# CKT-2000.net
KiCad netlist of a schematic drawn in EAGLE
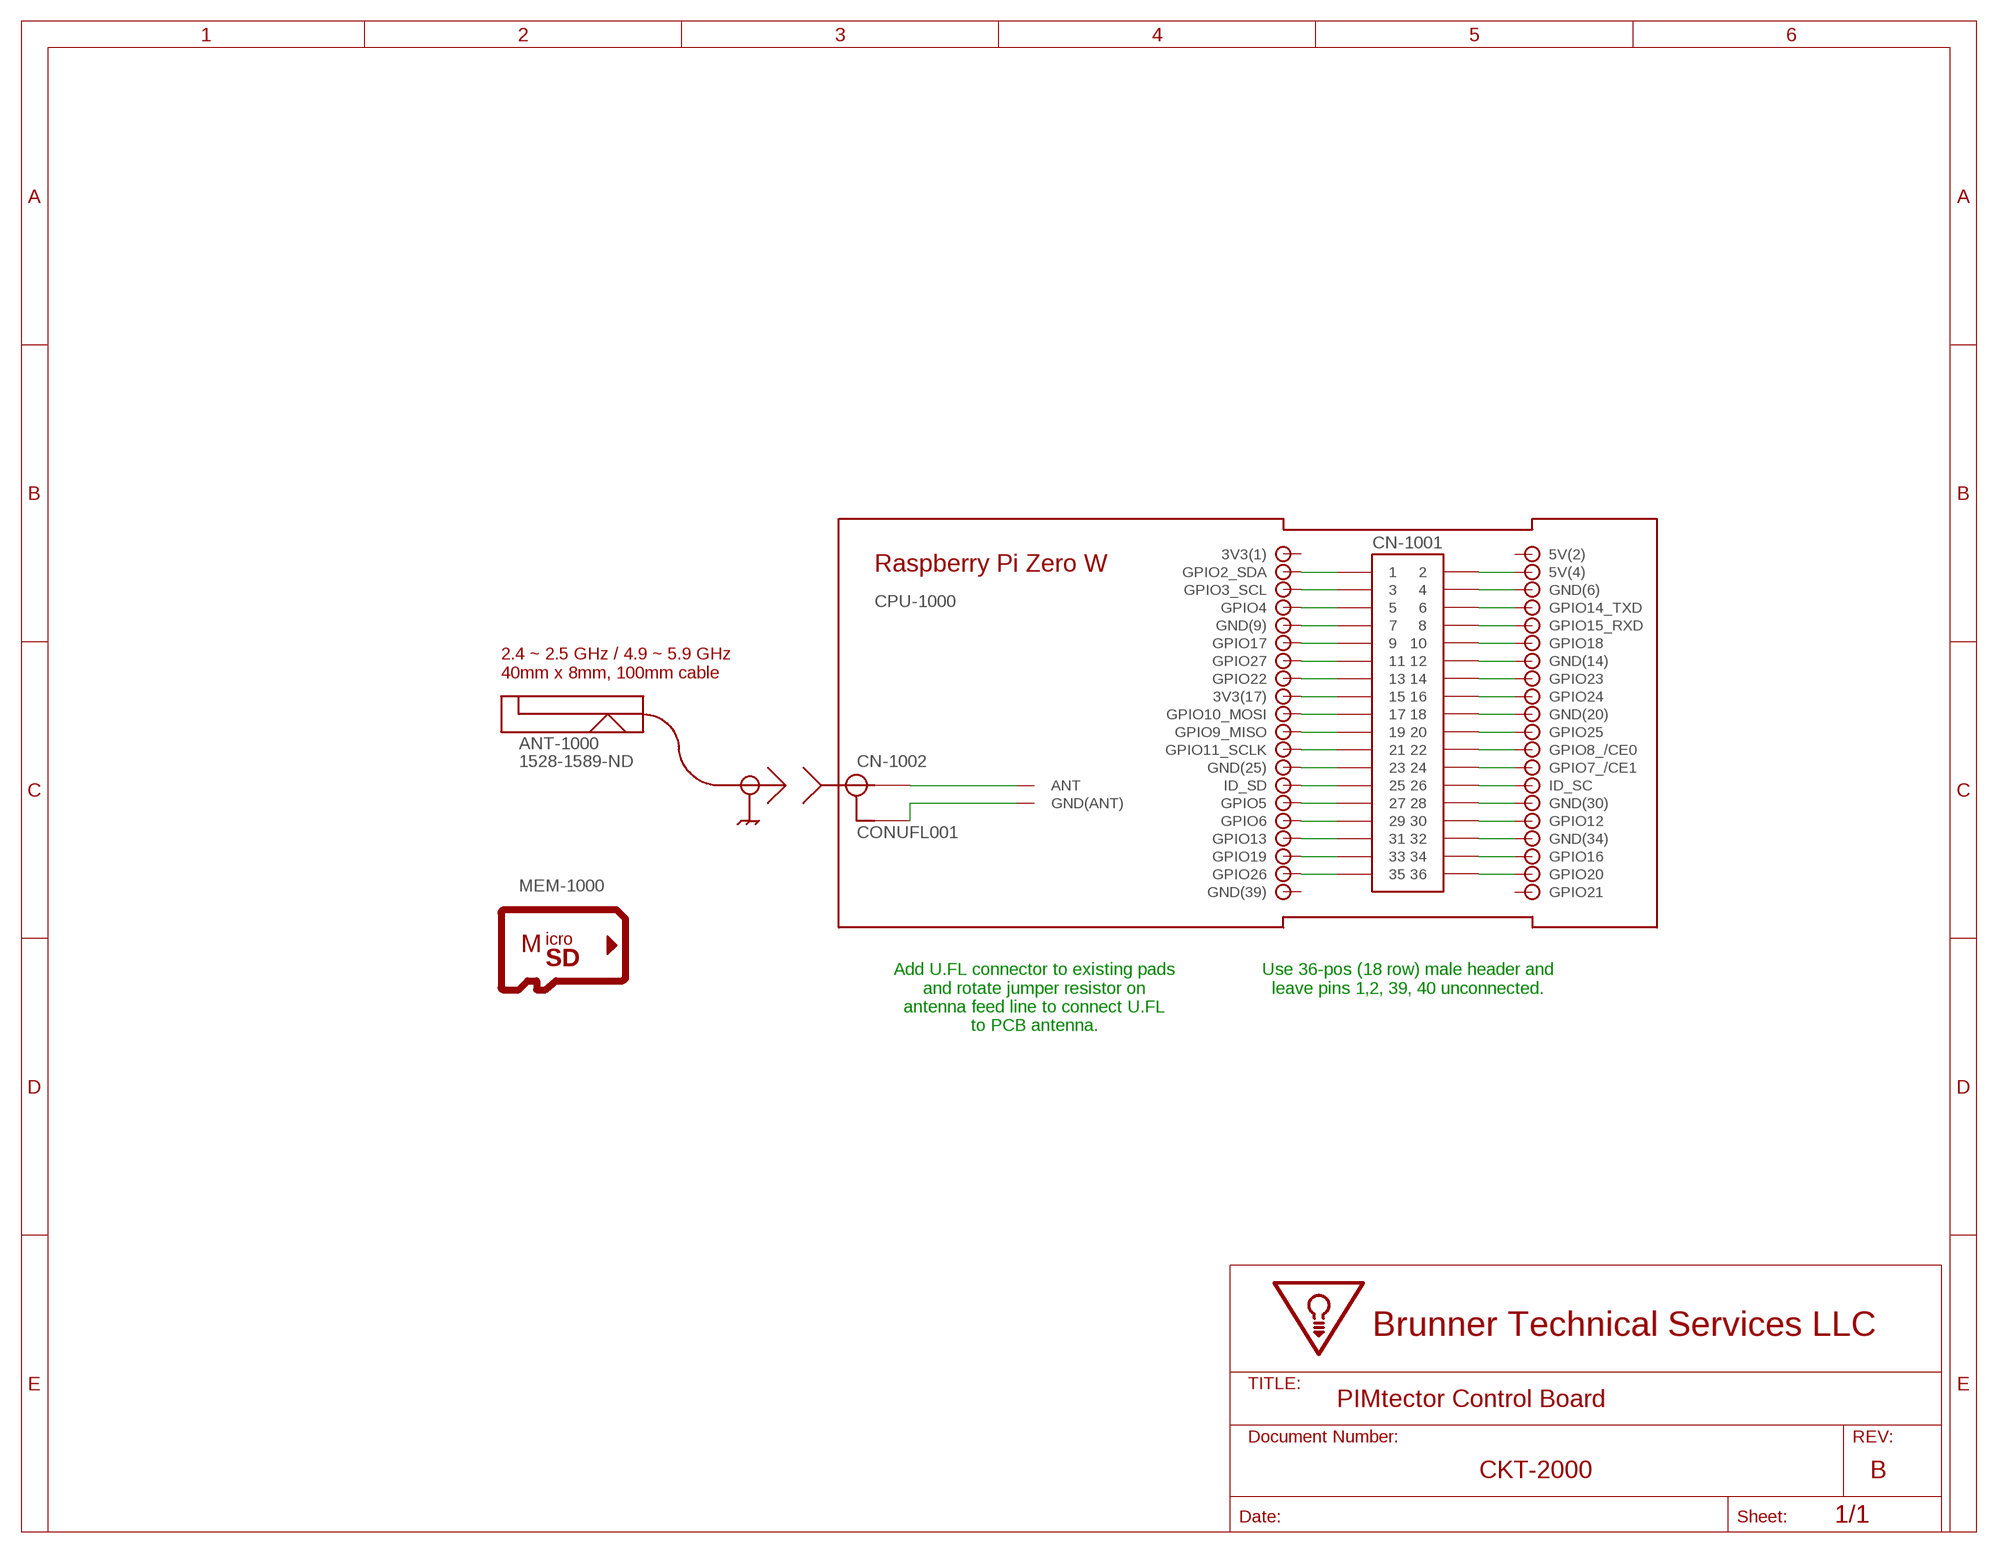
[diagram p0: schematic, sheet 1]

(export (version "E")
  (design (tool "Eeschema 10.0.6"))
  (components
    (comp (ref "CN-1001")
      (value "HEADER-FE-2X18")
      (footprint "eagle-import:HEADER-FE-2X18-TH")
      (libsource (lib "eagle-import") (part "HEADER-FE-2X18"))
    )
    (comp (ref "CN-1002")
      (value "CONUFL001")
      (footprint "eagle-import:CONUFL_UMC_SMD")
      (libsource (lib "eagle-import") (part "COAX_CONNECTORS"))
    )
    (comp (ref "CPU-1000")
      (value "RASPBERRY_PI_ZERO_W")
      (footprint "eagle-import:RASPBERRY_PI_ZERO_W")
      (libsource (lib "eagle-import") (part "RASPBERRY_PI_ZERO_W"))
    )
  )
  (nets
    (net (code "1") (name "/3V3(1)") (class "Default")
      (node (ref "CPU-1000") (pin "P$1") (pinfunction "3V3(1)_P$1") (pintype "power_in"))
    )
    (net (code "2") (name "/5V(2)") (class "Default")
      (node (ref "CPU-1000") (pin "P$2") (pinfunction "5V(2)_P$2") (pintype "power_in"))
    )
    (net (code "3") (name "/GND(39)") (class "Default")
      (node (ref "CPU-1000") (pin "P$39") (pinfunction "GND(39)_P$39") (pintype "power_in"))
    )
    (net (code "4") (name "Net-(CN-1001-1)") (class "Default")
      (node (ref "CN-1001") (pin "P$1") (pinfunction "1_P$1") (pintype "bidirectional"))
      (node (ref "CPU-1000") (pin "P$3") (pinfunction "GPIO2_SDA_P$3") (pintype "bidirectional"))
    )
    (net (code "5") (name "Net-(CN-1001-2)") (class "Default")
      (node (ref "CN-1001") (pin "P$2") (pinfunction "2_P$2") (pintype "bidirectional"))
      (node (ref "CPU-1000") (pin "P$4") (pinfunction "5V(4)_P$4") (pintype "power_in"))
    )
    (net (code "6") (name "Net-(CN-1001-3)") (class "Default")
      (node (ref "CN-1001") (pin "P$3") (pinfunction "3_P$3") (pintype "bidirectional"))
      (node (ref "CPU-1000") (pin "P$5") (pinfunction "GPIO3_SCL_P$5") (pintype "bidirectional"))
    )
    (net (code "7") (name "Net-(CN-1001-4)") (class "Default")
      (node (ref "CN-1001") (pin "P$4") (pinfunction "4_P$4") (pintype "bidirectional"))
      (node (ref "CPU-1000") (pin "P$6") (pinfunction "GND(6)_P$6") (pintype "power_in"))
    )
    (net (code "8") (name "Net-(CN-1001-5)") (class "Default")
      (node (ref "CN-1001") (pin "P$5") (pinfunction "5_P$5") (pintype "bidirectional"))
      (node (ref "CPU-1000") (pin "P$7") (pinfunction "GPIO4_P$7") (pintype "bidirectional"))
    )
    (net (code "9") (name "Net-(CN-1001-6)") (class "Default")
      (node (ref "CN-1001") (pin "P$6") (pinfunction "6_P$6") (pintype "bidirectional"))
      (node (ref "CPU-1000") (pin "P$8") (pinfunction "GPIO14_TXD_P$8") (pintype "bidirectional"))
    )
    (net (code "10") (name "Net-(CN-1001-7)") (class "Default")
      (node (ref "CN-1001") (pin "P$7") (pinfunction "7_P$7") (pintype "bidirectional"))
      (node (ref "CPU-1000") (pin "P$9") (pinfunction "GND(9)_P$9") (pintype "power_in"))
    )
    (net (code "11") (name "Net-(CN-1001-8)") (class "Default")
      (node (ref "CN-1001") (pin "P$8") (pinfunction "8_P$8") (pintype "bidirectional"))
      (node (ref "CPU-1000") (pin "P$10") (pinfunction "GPIO15_RXD_P$10") (pintype "bidirectional"))
    )
    (net (code "12") (name "Net-(CN-1001-9)") (class "Default")
      (node (ref "CN-1001") (pin "P$9") (pinfunction "9_P$9") (pintype "bidirectional"))
      (node (ref "CPU-1000") (pin "P$11") (pinfunction "GPIO17_P$11") (pintype "bidirectional"))
    )
    (net (code "13") (name "Net-(CN-1001-10)") (class "Default")
      (node (ref "CN-1001") (pin "P$10") (pinfunction "10_P$10") (pintype "bidirectional"))
      (node (ref "CPU-1000") (pin "P$12") (pinfunction "GPIO18_P$12") (pintype "bidirectional"))
    )
    (net (code "14") (name "Net-(CN-1001-11)") (class "Default")
      (node (ref "CN-1001") (pin "P$11") (pinfunction "11_P$11") (pintype "bidirectional"))
      (node (ref "CPU-1000") (pin "P$13") (pinfunction "GPIO27_P$13") (pintype "bidirectional"))
    )
    (net (code "15") (name "Net-(CN-1001-12)") (class "Default")
      (node (ref "CN-1001") (pin "P$12") (pinfunction "12_P$12") (pintype "bidirectional"))
      (node (ref "CPU-1000") (pin "P$14") (pinfunction "GND(14)_P$14") (pintype "power_in"))
    )
    (net (code "16") (name "Net-(CN-1001-13)") (class "Default")
      (node (ref "CN-1001") (pin "P$13") (pinfunction "13_P$13") (pintype "bidirectional"))
      (node (ref "CPU-1000") (pin "P$15") (pinfunction "GPIO22_P$15") (pintype "bidirectional"))
    )
    (net (code "17") (name "Net-(CN-1001-14)") (class "Default")
      (node (ref "CN-1001") (pin "P$14") (pinfunction "14_P$14") (pintype "bidirectional"))
      (node (ref "CPU-1000") (pin "P$16") (pinfunction "GPIO23_P$16") (pintype "bidirectional"))
    )
    (net (code "18") (name "Net-(CN-1001-15)") (class "Default")
      (node (ref "CN-1001") (pin "P$15") (pinfunction "15_P$15") (pintype "bidirectional"))
      (node (ref "CPU-1000") (pin "P$17") (pinfunction "3V3(17)_P$17") (pintype "power_in"))
    )
    (net (code "19") (name "Net-(CN-1001-16)") (class "Default")
      (node (ref "CN-1001") (pin "P$16") (pinfunction "16_P$16") (pintype "bidirectional"))
      (node (ref "CPU-1000") (pin "P$18") (pinfunction "GPIO24_P$18") (pintype "bidirectional"))
    )
    (net (code "20") (name "Net-(CN-1001-17)") (class "Default")
      (node (ref "CN-1001") (pin "P$17") (pinfunction "17_P$17") (pintype "bidirectional"))
      (node (ref "CPU-1000") (pin "P$19") (pinfunction "GPIO10_MOSI_P$19") (pintype "bidirectional"))
    )
    (net (code "21") (name "Net-(CN-1001-18)") (class "Default")
      (node (ref "CN-1001") (pin "P$18") (pinfunction "18_P$18") (pintype "bidirectional"))
      (node (ref "CPU-1000") (pin "P$20") (pinfunction "GND(20)_P$20") (pintype "bidirectional"))
    )
    (net (code "22") (name "Net-(CN-1001-19)") (class "Default")
      (node (ref "CN-1001") (pin "P$19") (pinfunction "19_P$19") (pintype "bidirectional"))
      (node (ref "CPU-1000") (pin "P$21") (pinfunction "GPIO9_MISO_P$21") (pintype "bidirectional"))
    )
    (net (code "23") (name "Net-(CN-1001-20)") (class "Default")
      (node (ref "CN-1001") (pin "P$20") (pinfunction "20_P$20") (pintype "bidirectional"))
      (node (ref "CPU-1000") (pin "P$22") (pinfunction "GPIO25_P$22") (pintype "bidirectional"))
    )
    (net (code "24") (name "Net-(CN-1001-21)") (class "Default")
      (node (ref "CN-1001") (pin "P$21") (pinfunction "21_P$21") (pintype "bidirectional"))
      (node (ref "CPU-1000") (pin "P$23") (pinfunction "GPIO11_SCLK_P$23") (pintype "bidirectional"))
    )
    (net (code "25") (name "Net-(CN-1001-22)") (class "Default")
      (node (ref "CN-1001") (pin "P$22") (pinfunction "22_P$22") (pintype "bidirectional"))
      (node (ref "CPU-1000") (pin "P$24") (pinfunction "GPIO8_/CE0_P$24") (pintype "bidirectional"))
    )
    (net (code "26") (name "Net-(CN-1001-23)") (class "Default")
      (node (ref "CN-1001") (pin "P$23") (pinfunction "23_P$23") (pintype "bidirectional"))
      (node (ref "CPU-1000") (pin "P$25") (pinfunction "GND(25)_P$25") (pintype "power_in"))
    )
    (net (code "27") (name "Net-(CN-1001-24)") (class "Default")
      (node (ref "CN-1001") (pin "P$24") (pinfunction "24_P$24") (pintype "bidirectional"))
      (node (ref "CPU-1000") (pin "P$26") (pinfunction "GPIO7_/CE1_P$26") (pintype "bidirectional"))
    )
    (net (code "28") (name "Net-(CN-1001-25)") (class "Default")
      (node (ref "CN-1001") (pin "P$25") (pinfunction "25_P$25") (pintype "bidirectional"))
      (node (ref "CPU-1000") (pin "P$27") (pinfunction "ID_SD_P$27") (pintype "bidirectional"))
    )
    (net (code "29") (name "Net-(CN-1001-26)") (class "Default")
      (node (ref "CN-1001") (pin "P$26") (pinfunction "26_P$26") (pintype "bidirectional"))
      (node (ref "CPU-1000") (pin "P$28") (pinfunction "ID_SC_P$28") (pintype "bidirectional"))
    )
    (net (code "30") (name "Net-(CN-1001-27)") (class "Default")
      (node (ref "CN-1001") (pin "P$27") (pinfunction "27_P$27") (pintype "bidirectional"))
      (node (ref "CPU-1000") (pin "P$29") (pinfunction "GPIO5_P$29") (pintype "bidirectional"))
    )
    (net (code "31") (name "Net-(CN-1001-28)") (class "Default")
      (node (ref "CN-1001") (pin "P$28") (pinfunction "28_P$28") (pintype "bidirectional"))
      (node (ref "CPU-1000") (pin "P$30") (pinfunction "GND(30)_P$30") (pintype "bidirectional"))
    )
    (net (code "32") (name "Net-(CN-1001-29)") (class "Default")
      (node (ref "CN-1001") (pin "P$29") (pinfunction "29_P$29") (pintype "bidirectional"))
      (node (ref "CPU-1000") (pin "P$31") (pinfunction "GPIO6_P$31") (pintype "bidirectional"))
    )
    (net (code "33") (name "Net-(CN-1001-30)") (class "Default")
      (node (ref "CN-1001") (pin "P$30") (pinfunction "30_P$30") (pintype "bidirectional"))
      (node (ref "CPU-1000") (pin "P$32") (pinfunction "GPIO12_P$32") (pintype "bidirectional"))
    )
    (net (code "34") (name "Net-(CN-1001-31)") (class "Default")
      (node (ref "CN-1001") (pin "P$31") (pinfunction "31_P$31") (pintype "bidirectional"))
      (node (ref "CPU-1000") (pin "P$33") (pinfunction "GPIO13_P$33") (pintype "bidirectional"))
    )
    (net (code "35") (name "Net-(CN-1001-32)") (class "Default")
      (node (ref "CN-1001") (pin "P$32") (pinfunction "32_P$32") (pintype "bidirectional"))
      (node (ref "CPU-1000") (pin "P$34") (pinfunction "GND(34)_P$34") (pintype "bidirectional"))
    )
    (net (code "36") (name "Net-(CN-1001-33)") (class "Default")
      (node (ref "CN-1001") (pin "P$33") (pinfunction "33_P$33") (pintype "bidirectional"))
      (node (ref "CPU-1000") (pin "P$35") (pinfunction "GPIO19_P$35") (pintype "bidirectional"))
    )
    (net (code "37") (name "Net-(CN-1001-34)") (class "Default")
      (node (ref "CN-1001") (pin "P$34") (pinfunction "34_P$34") (pintype "bidirectional"))
      (node (ref "CPU-1000") (pin "P$36") (pinfunction "GPIO16_P$36") (pintype "bidirectional"))
    )
    (net (code "38") (name "Net-(CN-1001-35)") (class "Default")
      (node (ref "CN-1001") (pin "P$35") (pinfunction "35_P$35") (pintype "bidirectional"))
      (node (ref "CPU-1000") (pin "P$37") (pinfunction "GPIO26_P$37") (pintype "bidirectional"))
    )
    (net (code "39") (name "Net-(CN-1001-36)") (class "Default")
      (node (ref "CN-1001") (pin "P$36") (pinfunction "36_P$36") (pintype "bidirectional"))
      (node (ref "CPU-1000") (pin "P$38") (pinfunction "GPIO20_P$38") (pintype "bidirectional"))
    )
    (net (code "40") (name "Net-(CN-1002-P$2-PadP$3)") (class "Default")
      (node (ref "CN-1002") (pin "P$2") (pinfunction "P$2_P$2") (pintype "bidirectional"))
      (node (ref "CN-1002") (pin "P$3") (pinfunction "P$2_P$3") (pintype "bidirectional"))
      (node (ref "CPU-1000") (pin "P$42") (pinfunction "GND(ANT)_P$42") (pintype "bidirectional"))
      (node (ref "CPU-1000") (pin "P$43") (pinfunction "GND(ANT)_P$43") (pintype "bidirectional"))
    )
    (net (code "41") (name "Net-(CPU-1000-ANT)") (class "Default")
      (node (ref "CN-1002") (pin "P$1") (pinfunction "P$1_P$1") (pintype "bidirectional"))
      (node (ref "CPU-1000") (pin "P$41") (pinfunction "ANT_P$41") (pintype "bidirectional"))
    )
    (net (code "42") (name "unconnected-(CPU-1000-GPIO21-PadP$40)") (class "Default")
      (node (ref "CPU-1000") (pin "P$40") (pinfunction "GPIO21_P$40") (pintype "bidirectional"))
    )
  )
)
